# OpenBook_Schematic.net
KiCad netlist of a schematic drawn in EAGLE
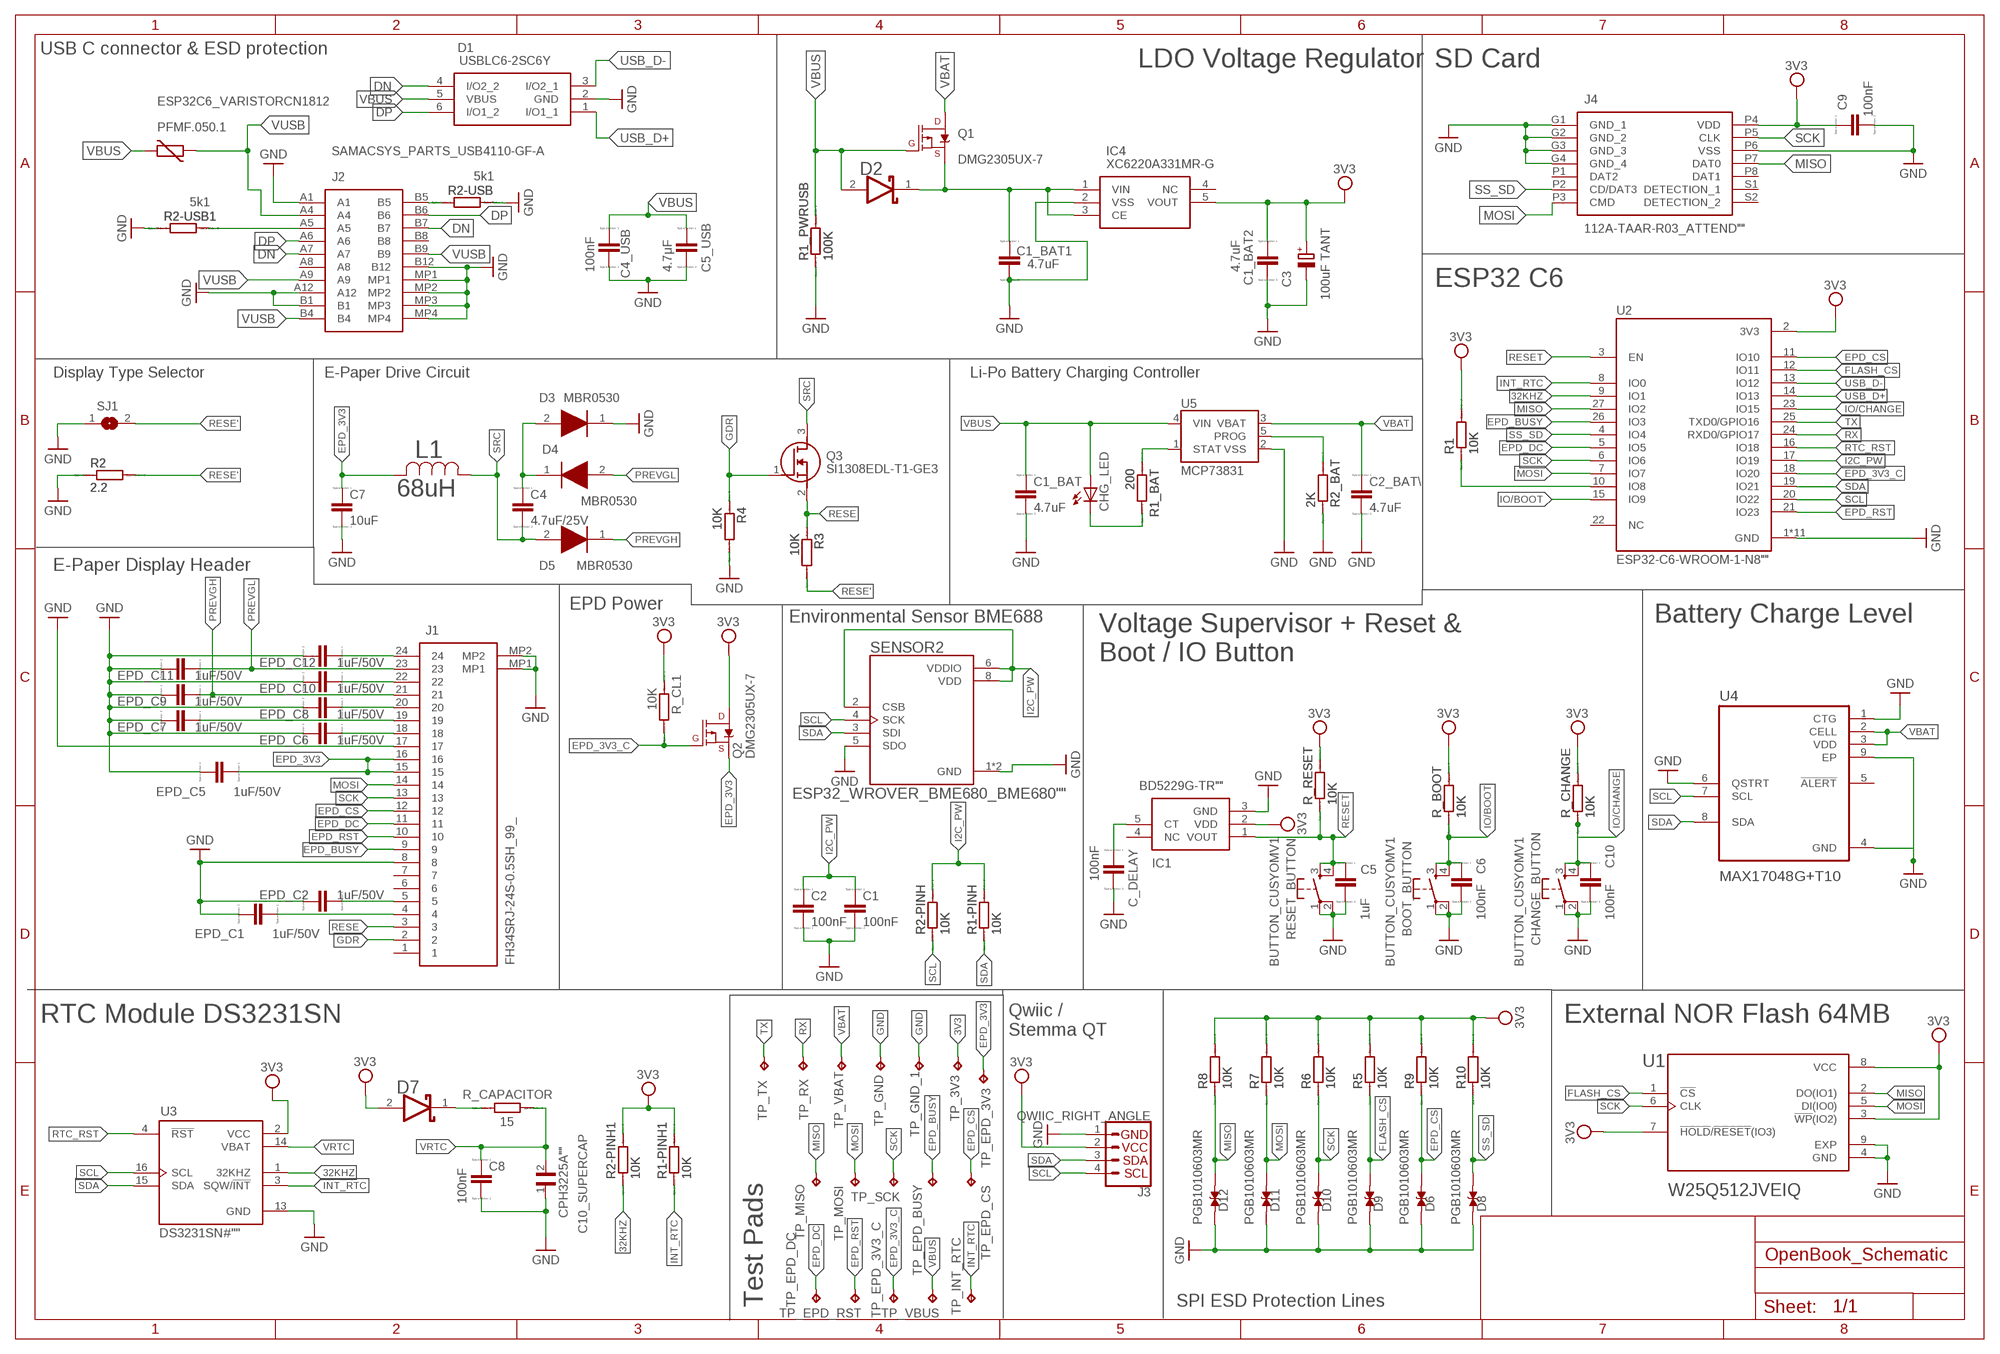
[diagram p0: schematic, sheet 1]

(export (version "E")
  (design (tool "Eeschema 10.0.6"))
  (components
    (comp (ref "BOOT_BUTTON")
      (value "BUTTON_CUSYOMV1")
      (footprint "eagle-import:MYBUTTON")
      (libsource (lib "eagle-import") (part "BUTTON_CUSYOMV1"))
    )
    (comp (ref "C1")
      (value "100nF")
      (footprint "eagle-import:ESP32_WROVER_EAGLE-LTSPICE_C0402")
      (libsource (lib "eagle-import") (part "ESP32_WROVER_EAGLE-LTSPICE_CC0402"))
    )
    (comp (ref "C1_BAT")
      (value "4.7uF")
      (footprint "eagle-import:ESP32_WROVER_EAGLE-LTSPICE_C0402")
      (libsource (lib "eagle-import") (part "ESP32_WROVER_EAGLE-LTSPICE_CC0402"))
    )
    (comp (ref "C1_BAT1")
      (value "4.7uF")
      (footprint "eagle-import:ESP32_WROVER_EAGLE-LTSPICE_C0402")
      (libsource (lib "eagle-import") (part "ESP32_WROVER_EAGLE-LTSPICE_CC0402"))
    )
    (comp (ref "C1_BAT2")
      (value "4.7uF")
      (footprint "eagle-import:ESP32_WROVER_EAGLE-LTSPICE_C0402")
      (libsource (lib "eagle-import") (part "ESP32_WROVER_EAGLE-LTSPICE_CC0402"))
    )
    (comp (ref "C2")
      (value "100nF")
      (footprint "eagle-import:ESP32_WROVER_EAGLE-LTSPICE_C0402")
      (libsource (lib "eagle-import") (part "ESP32_WROVER_EAGLE-LTSPICE_CC0402"))
    )
    (comp (ref "C2_BAT\\")
      (value "4.7uF")
      (footprint "eagle-import:ESP32_WROVER_EAGLE-LTSPICE_C0402")
      (libsource (lib "eagle-import") (part "ESP32_WROVER_EAGLE-LTSPICE_CC0402"))
    )
    (comp (ref "C3")
      (value "100uF TANT")
      (footprint "eagle-import:RCL_CT3528")
      (libsource (lib "eagle-import") (part "RCL_CPOL-EUCT3528"))
    )
    (comp (ref "C4")
      (value "4.7uF/25V")
      (footprint "eagle-import:ESP32_WROVER_EAGLE-LTSPICE_C0402")
      (libsource (lib "eagle-import") (part "ESP32_WROVER_EAGLE-LTSPICE_CC0402"))
    )
    (comp (ref "C4_USB")
      (value "100nF")
      (footprint "eagle-import:ESP32_WROVER_EAGLE-LTSPICE_C0402")
      (libsource (lib "eagle-import") (part "ESP32_WROVER_EAGLE-LTSPICE_CC0402"))
    )
    (comp (ref "C5")
      (value "1uF")
      (footprint "eagle-import:ESP32_WROVER_EAGLE-LTSPICE_C0402")
      (libsource (lib "eagle-import") (part "ESP32_WROVER_EAGLE-LTSPICE_CC0402"))
    )
    (comp (ref "C5_USB")
      (value "4.7μF")
      (footprint "eagle-import:ESP32_WROVER_EAGLE-LTSPICE_C0402")
      (libsource (lib "eagle-import") (part "ESP32_WROVER_EAGLE-LTSPICE_CC0402"))
    )
    (comp (ref "C6")
      (value "100nF")
      (footprint "eagle-import:ESP32_WROVER_EAGLE-LTSPICE_C0402")
      (libsource (lib "eagle-import") (part "ESP32_WROVER_EAGLE-LTSPICE_CC0402"))
    )
    (comp (ref "C7")
      (value "10uF")
      (footprint "eagle-import:ESP32_WROVER_EAGLE-LTSPICE_C0402")
      (libsource (lib "eagle-import") (part "ESP32_WROVER_EAGLE-LTSPICE_CC0402"))
    )
    (comp (ref "C8")
      (value "100nF")
      (footprint "eagle-import:ESP32_WROVER_EAGLE-LTSPICE_C0402")
      (libsource (lib "eagle-import") (part "ESP32_WROVER_EAGLE-LTSPICE_CC0402"))
    )
    (comp (ref "C9")
      (value "100nF")
      (footprint "eagle-import:ESP32_WROVER_EAGLE-LTSPICE_C0402")
      (libsource (lib "eagle-import") (part "EAGLE-LTSPICE_CC0402"))
    )
    (comp (ref "C10")
      (value "100nF")
      (footprint "eagle-import:ESP32_WROVER_EAGLE-LTSPICE_C0402")
      (libsource (lib "eagle-import") (part "ESP32_WROVER_EAGLE-LTSPICE_CC0402"))
    )
    (comp (ref "C10_SUPERCAP")
      (value "CPH3225A\"\"")
      (footprint "eagle-import:CAPCP3225X100N")
      (libsource (lib "eagle-import") (part "CPH3225A{dblquote}{dblquote}"))
    )
    (comp (ref "CHANGE_BUTTON")
      (value "BUTTON_CUSYOMV1")
      (footprint "eagle-import:MYBUTTON")
      (libsource (lib "eagle-import") (part "BUTTON_CUSYOMV1"))
    )
    (comp (ref "CHG_LED")
      (value "ADAFRUIT_LEDCHIP-LED0603")
      (footprint "eagle-import:ADAFRUIT_CHIP-LED0603")
      (libsource (lib "eagle-import") (part "ADAFRUIT_LEDCHIP-LED0603"))
    )
    (comp (ref "C_DELAY")
      (value "100nF")
      (footprint "eagle-import:ESP32_WROVER_EAGLE-LTSPICE_C0402")
      (libsource (lib "eagle-import") (part "ESP32_WROVER_EAGLE-LTSPICE_CC0402"))
    )
    (comp (ref "D1")
      (value "USBLC6-2SC6Y")
      (footprint "eagle-import:SOT95P280X145-6N")
      (libsource (lib "eagle-import") (part "USBLC6-2SC6Y"))
    )
    (comp (ref "D2")
      (value "ESP32_WROVER_AVX---SD0805S020S1R0_AVX_SD0805S020S1R0_0_0AVX_SD0805S020S1R0_0_0")
      (footprint "eagle-import:ESP32_WROVER_AVX---SD0805S020S1R0_AVX_SD0805S020S1R0_0")
      (libsource (lib "eagle-import") (part "ESP32_WROVER_AVX---SD0805S020S1R0_AVX_SD0805S020S1R0_0_0AVX_SD0805S020S1R0_0_0"))
    )
    (comp (ref "D3")
      (value "MBR0530")
      (footprint "eagle-import:SOD3716X135N")
      (libsource (lib "eagle-import") (part "MBR0530"))
    )
    (comp (ref "D4")
      (value "MBR0530")
      (footprint "eagle-import:SOD3716X135N")
      (libsource (lib "eagle-import") (part "MBR0530"))
    )
    (comp (ref "D5")
      (value "MBR0530")
      (footprint "eagle-import:SOD3716X135N")
      (libsource (lib "eagle-import") (part "MBR0530"))
    )
    (comp (ref "D6")
      (value "PGB1010603MR")
      (footprint "eagle-import:DIOC1608X36N")
      (libsource (lib "eagle-import") (part "PGB1010603MR"))
    )
    (comp (ref "D7")
      (value "ESP32_WROVER_AVX---SD0805S020S1R0_AVX_SD0805S020S1R0_0_0AVX_SD0805S020S1R0_0_0")
      (footprint "eagle-import:ESP32_WROVER_AVX---SD0805S020S1R0_AVX_SD0805S020S1R0_0")
      (libsource (lib "eagle-import") (part "ESP32_WROVER_AVX---SD0805S020S1R0_AVX_SD0805S020S1R0_0_0AVX_SD0805S020S1R0_0_0"))
    )
    (comp (ref "D8")
      (value "PGB1010603MR")
      (footprint "eagle-import:DIOC1608X36N")
      (libsource (lib "eagle-import") (part "PGB1010603MR"))
    )
    (comp (ref "D9")
      (value "PGB1010603MR")
      (footprint "eagle-import:DIOC1608X36N")
      (libsource (lib "eagle-import") (part "PGB1010603MR"))
    )
    (comp (ref "D10")
      (value "PGB1010603MR")
      (footprint "eagle-import:DIOC1608X36N")
      (libsource (lib "eagle-import") (part "PGB1010603MR"))
    )
    (comp (ref "D11")
      (value "PGB1010603MR")
      (footprint "eagle-import:DIOC1608X36N")
      (libsource (lib "eagle-import") (part "PGB1010603MR"))
    )
    (comp (ref "D12")
      (value "PGB1010603MR")
      (footprint "eagle-import:DIOC1608X36N")
      (libsource (lib "eagle-import") (part "PGB1010603MR"))
    )
    (comp (ref "EPD_C1")
      (value "1uF/50V")
      (footprint "eagle-import:ESP32_WROVER_EAGLE-LTSPICE_C0402")
      (libsource (lib "eagle-import") (part "ESP32_WROVER_EAGLE-LTSPICE_CC0402"))
    )
    (comp (ref "EPD_C2")
      (value "1uF/50V")
      (footprint "eagle-import:ESP32_WROVER_EAGLE-LTSPICE_C0402")
      (libsource (lib "eagle-import") (part "ESP32_WROVER_EAGLE-LTSPICE_CC0402"))
    )
    (comp (ref "EPD_C5")
      (value "1uF/50V")
      (footprint "eagle-import:ESP32_WROVER_EAGLE-LTSPICE_C0402")
      (libsource (lib "eagle-import") (part "ESP32_WROVER_EAGLE-LTSPICE_CC0402"))
    )
    (comp (ref "EPD_C6")
      (value "1uF/50V")
      (footprint "eagle-import:ESP32_WROVER_EAGLE-LTSPICE_C0402")
      (libsource (lib "eagle-import") (part "ESP32_WROVER_EAGLE-LTSPICE_CC0402"))
    )
    (comp (ref "EPD_C7")
      (value "1uF/50V")
      (footprint "eagle-import:ESP32_WROVER_EAGLE-LTSPICE_C0402")
      (libsource (lib "eagle-import") (part "ESP32_WROVER_EAGLE-LTSPICE_CC0402"))
    )
    (comp (ref "EPD_C8")
      (value "1uF/50V")
      (footprint "eagle-import:ESP32_WROVER_EAGLE-LTSPICE_C0402")
      (libsource (lib "eagle-import") (part "ESP32_WROVER_EAGLE-LTSPICE_CC0402"))
    )
    (comp (ref "EPD_C9")
      (value "1uF/50V")
      (footprint "eagle-import:ESP32_WROVER_EAGLE-LTSPICE_C0402")
      (libsource (lib "eagle-import") (part "ESP32_WROVER_EAGLE-LTSPICE_CC0402"))
    )
    (comp (ref "EPD_C10")
      (value "1uF/50V")
      (footprint "eagle-import:ESP32_WROVER_EAGLE-LTSPICE_C0402")
      (libsource (lib "eagle-import") (part "ESP32_WROVER_EAGLE-LTSPICE_CC0402"))
    )
    (comp (ref "EPD_C11")
      (value "1uF/50V")
      (footprint "eagle-import:ESP32_WROVER_EAGLE-LTSPICE_C0402")
      (libsource (lib "eagle-import") (part "ESP32_WROVER_EAGLE-LTSPICE_CC0402"))
    )
    (comp (ref "EPD_C12")
      (value "1uF/50V")
      (footprint "eagle-import:ESP32_WROVER_EAGLE-LTSPICE_C0402")
      (libsource (lib "eagle-import") (part "ESP32_WROVER_EAGLE-LTSPICE_CC0402"))
    )
    (comp (ref "IC1")
      (value "BD5229G-TR\"\"")
      (footprint "eagle-import:SOT95P280X125-5N")
      (libsource (lib "eagle-import") (part "BD5229G-TR{dblquote}{dblquote}"))
    )
    (comp (ref "IC4")
      (value "XC6220A331MR-G")
      (footprint "eagle-import:SOT95P280X120-5N")
      (libsource (lib "eagle-import") (part "XC6220A331MR-G"))
    )
    (comp (ref "J1")
      (value "FH34SRJ-24S-0.5SH_99_")
      (footprint "eagle-import:FH34SRJ24S05SH99")
      (libsource (lib "eagle-import") (part "FH34SRJ-24S-0.5SH_99_"))
    )
    (comp (ref "J2")
      (value "SAMACSYS_PARTS_USB4110-GF-A")
      (footprint "eagle-import:SAMACSYS_PARTS_USB4110GFA")
      (libsource (lib "eagle-import") (part "SAMACSYS_PARTS_USB4110-GF-A"))
    )
    (comp (ref "J3")
      (value "QWIIC_RIGHT_ANGLE")
      (footprint "eagle-import:JST04_1MM_RA")
      (libsource (lib "eagle-import") (part "QWIIC_CONNECTORJS-1MM"))
    )
    (comp (ref "J4")
      (value "112A-TAAR-R03_ATTEND\"\"")
      (footprint "eagle-import:112ATAARR03ATTEND")
      (libsource (lib "eagle-import") (part "112A-TAAR-R03_ATTEND{dblquote}{dblquote}"))
    )
    (comp (ref "L1")
      (value "68uH")
      (footprint "eagle-import:IND_4828-WE-TPC_WRE")
      (libsource (lib "eagle-import") (part "744043680IND_4828-WE-TPC_WRE"))
    )
    (comp (ref "PFMF.050.1")
      (value "ESP32C6_VARISTORCN1812")
      (footprint "eagle-import:ESP32C6_VARISTOR_CT_CN1812")
      (libsource (lib "eagle-import") (part "ESP32C6_VARISTORCN1812"))
    )
    (comp (ref "Q1")
      (value "20V/4.2A/52mΩ/1.4W")
      (footprint "eagle-import:ESP32_WROVER_SPARKFUN-DISCRETESEMI_SOT23-3")
      (fields (field (name "PARTNAME") "DMG2305UX-7"))
      (libsource (lib "eagle-import") (part "ESP32_WROVER_SPARKFUN-DISCRETESEMI_MOSFET_PCH-DMG2305UX-7"))
    )
    (comp (ref "Q2")
      (value "20V/4.2A/52mΩ/1.4W")
      (footprint "eagle-import:ESP32_WROVER_SPARKFUN-DISCRETESEMI_SOT23-3")
      (fields (field (name "PARTNAME") "DMG2305UX-7"))
      (libsource (lib "eagle-import") (part "ESP32_WROVER_SPARKFUN-DISCRETESEMI_MOSFET_PCH-DMG2305UX-7"))
    )
    (comp (ref "Q3")
      (value "SI1308EDL-T1-GE3")
      (footprint "eagle-import:SOT65P210X110-3N")
      (libsource (lib "eagle-import") (part "SI1308EDL-T1-GE3"))
    )
    (comp (ref "R1")
      (value "10K")
      (footprint "eagle-import:ESP32_WROVER_EAGLE-LTSPICE_R0402")
      (libsource (lib "eagle-import") (part "ESP32_WROVER_EAGLE-LTSPICE_RR0402"))
    )
    (comp (ref "R1-PINH")
      (value "10K")
      (footprint "eagle-import:ESP32_WROVER_EAGLE-LTSPICE_R0402")
      (libsource (lib "eagle-import") (part "ESP32_WROVER_EAGLE-LTSPICE_RR0402"))
    )
    (comp (ref "R1-PINH1")
      (value "10K")
      (footprint "eagle-import:ESP32_WROVER_EAGLE-LTSPICE_R0402")
      (libsource (lib "eagle-import") (part "ESP32_WROVER_EAGLE-LTSPICE_RR0402"))
    )
    (comp (ref "R1_BAT")
      (value "200")
      (footprint "eagle-import:ESP32_WROVER_EAGLE-LTSPICE_R0402")
      (libsource (lib "eagle-import") (part "ESP32_WROVER_EAGLE-LTSPICE_RR0402"))
    )
    (comp (ref "R1_PWRUSB")
      (value "100K")
      (footprint "eagle-import:ESP32_WROVER_EAGLE-LTSPICE_R0402")
      (libsource (lib "eagle-import") (part "ESP32_WROVER_EAGLE-LTSPICE_RR0402"))
    )
    (comp (ref "R2")
      (value "2.2")
      (footprint "eagle-import:ESP32_WROVER_EAGLE-LTSPICE_R0402")
      (libsource (lib "eagle-import") (part "ESP32_WROVER_EAGLE-LTSPICE_RR0402"))
    )
    (comp (ref "R2-PINH")
      (value "10K")
      (footprint "eagle-import:ESP32_WROVER_EAGLE-LTSPICE_R0402")
      (libsource (lib "eagle-import") (part "ESP32_WROVER_EAGLE-LTSPICE_RR0402"))
    )
    (comp (ref "R2-PINH1")
      (value "10K")
      (footprint "eagle-import:ESP32_WROVER_EAGLE-LTSPICE_R0402")
      (libsource (lib "eagle-import") (part "ESP32_WROVER_EAGLE-LTSPICE_RR0402"))
    )
    (comp (ref "R2-USB")
      (value "5k1")
      (footprint "eagle-import:ESP32_WROVER_EAGLE-LTSPICE_R0402")
      (libsource (lib "eagle-import") (part "ESP32_WROVER_EAGLE-LTSPICE_RR0402"))
    )
    (comp (ref "R2-USB1")
      (value "5k1")
      (footprint "eagle-import:ESP32_WROVER_EAGLE-LTSPICE_R0402")
      (libsource (lib "eagle-import") (part "ESP32_WROVER_EAGLE-LTSPICE_RR0402"))
    )
    (comp (ref "R2_BAT")
      (value "2K")
      (footprint "eagle-import:ESP32_WROVER_EAGLE-LTSPICE_R0402")
      (libsource (lib "eagle-import") (part "ESP32_WROVER_EAGLE-LTSPICE_RR0402"))
    )
    (comp (ref "R3")
      (value "10K")
      (footprint "eagle-import:ESP32_WROVER_EAGLE-LTSPICE_R0402")
      (libsource (lib "eagle-import") (part "ESP32_WROVER_EAGLE-LTSPICE_RR0402"))
    )
    (comp (ref "R4")
      (value "10K")
      (footprint "eagle-import:ESP32_WROVER_EAGLE-LTSPICE_R0402")
      (libsource (lib "eagle-import") (part "ESP32_WROVER_EAGLE-LTSPICE_RR0402"))
    )
    (comp (ref "R5")
      (value "10K")
      (footprint "eagle-import:ESP32_WROVER_EAGLE-LTSPICE_R0402")
      (libsource (lib "eagle-import") (part "ESP32_WROVER_EAGLE-LTSPICE_RR0402"))
    )
    (comp (ref "R6")
      (value "10K")
      (footprint "eagle-import:ESP32_WROVER_EAGLE-LTSPICE_R0402")
      (libsource (lib "eagle-import") (part "ESP32_WROVER_EAGLE-LTSPICE_RR0402"))
    )
    (comp (ref "R7")
      (value "10K")
      (footprint "eagle-import:ESP32_WROVER_EAGLE-LTSPICE_R0402")
      (libsource (lib "eagle-import") (part "ESP32_WROVER_EAGLE-LTSPICE_RR0402"))
    )
    (comp (ref "R8")
      (value "10K")
      (footprint "eagle-import:ESP32_WROVER_EAGLE-LTSPICE_R0402")
      (libsource (lib "eagle-import") (part "ESP32_WROVER_EAGLE-LTSPICE_RR0402"))
    )
    (comp (ref "R9")
      (value "10K")
      (footprint "eagle-import:ESP32_WROVER_EAGLE-LTSPICE_R0402")
      (libsource (lib "eagle-import") (part "ESP32_WROVER_EAGLE-LTSPICE_RR0402"))
    )
    (comp (ref "R10")
      (value "10K")
      (footprint "eagle-import:ESP32_WROVER_EAGLE-LTSPICE_R0402")
      (libsource (lib "eagle-import") (part "ESP32_WROVER_EAGLE-LTSPICE_RR0402"))
    )
    (comp (ref "RESET_BUTTON")
      (value "BUTTON_CUSYOMV1")
      (footprint "eagle-import:MYBUTTON")
      (libsource (lib "eagle-import") (part "BUTTON_CUSYOMV1"))
    )
    (comp (ref "R_BOOT")
      (value "10K")
      (footprint "eagle-import:ESP32_WROVER_EAGLE-LTSPICE_R0402")
      (libsource (lib "eagle-import") (part "ESP32_WROVER_EAGLE-LTSPICE_RR0402"))
    )
    (comp (ref "R_CAPACITOR")
      (value "15")
      (footprint "eagle-import:ESP32_WROVER_EAGLE-LTSPICE_R0402")
      (libsource (lib "eagle-import") (part "ESP32_WROVER_EAGLE-LTSPICE_RR0402"))
    )
    (comp (ref "R_CHANGE")
      (value "10K")
      (footprint "eagle-import:ESP32_WROVER_EAGLE-LTSPICE_R0402")
      (libsource (lib "eagle-import") (part "ESP32_WROVER_EAGLE-LTSPICE_RR0402"))
    )
    (comp (ref "R_CL1")
      (value "10K")
      (footprint "eagle-import:ESP32_WROVER_EAGLE-LTSPICE_R0402")
      (libsource (lib "eagle-import") (part "ESP32_WROVER_EAGLE-LTSPICE_RR0402"))
    )
    (comp (ref "R_RESET")
      (value "10K")
      (footprint "eagle-import:ESP32_WROVER_EAGLE-LTSPICE_R0402")
      (libsource (lib "eagle-import") (part "ESP32_WROVER_EAGLE-LTSPICE_RR0402"))
    )
    (comp (ref "SENSOR2")
      (value "ESP32_WROVER_BME680_BME680\"\"")
      (footprint "eagle-import:ESP32_WROVER_BME680_PSON80P300X300X100-8N")
      (libsource (lib "eagle-import") (part "ESP32_WROVER_BME680_BME680{dblquote}{dblquote}"))
    )
    (comp (ref "SJ1") (value "SJ") (footprint "eagle-import:SJ") (libsource (lib "eagle-import") (part "SJ")))
    (comp (ref "TP_3V3")
      (value "TPTP20R")
      (footprint "eagle-import:TP20R")
      (libsource (lib "eagle-import") (part "TPTP20R"))
    )
    (comp (ref "TP_EPD_3V3")
      (value "TPTP20R")
      (footprint "eagle-import:TP20R")
      (libsource (lib "eagle-import") (part "TPTP20R"))
    )
    (comp (ref "TP_EPD_3V3_C")
      (value "TPTP20R")
      (footprint "eagle-import:TP20R")
      (libsource (lib "eagle-import") (part "TPTP20R"))
    )
    (comp (ref "TP_EPD_BUSY")
      (value "TPTP20R")
      (footprint "eagle-import:TP20R")
      (libsource (lib "eagle-import") (part "TPTP20R"))
    )
    (comp (ref "TP_EPD_CS")
      (value "TPTP20R")
      (footprint "eagle-import:TP20R")
      (libsource (lib "eagle-import") (part "TPTP20R"))
    )
    (comp (ref "TP_EPD_DC")
      (value "TPTP20R")
      (footprint "eagle-import:TP20R")
      (libsource (lib "eagle-import") (part "TPTP20R"))
    )
    (comp (ref "TP_EPD_RST")
      (value "TPTP20R")
      (footprint "eagle-import:TP20R")
      (libsource (lib "eagle-import") (part "TPTP20R"))
    )
    (comp (ref "TP_GND")
      (value "TPTP20R")
      (footprint "eagle-import:TP20R")
      (libsource (lib "eagle-import") (part "TPTP20R"))
    )
    (comp (ref "TP_GND_1")
      (value "TPTP20R")
      (footprint "eagle-import:TP20R")
      (libsource (lib "eagle-import") (part "TPTP20R"))
    )
    (comp (ref "TP_INT_RTC")
      (value "TPTP20R")
      (footprint "eagle-import:TP20R")
      (libsource (lib "eagle-import") (part "TPTP20R"))
    )
    (comp (ref "TP_MISO")
      (value "TPTP20R")
      (footprint "eagle-import:TP20R")
      (libsource (lib "eagle-import") (part "TPTP20R"))
    )
    (comp (ref "TP_MOSI")
      (value "TPTP20R")
      (footprint "eagle-import:TP20R")
      (libsource (lib "eagle-import") (part "TPTP20R"))
    )
    (comp (ref "TP_RX")
      (value "TPTP20R")
      (footprint "eagle-import:TP20R")
      (libsource (lib "eagle-import") (part "TPTP20R"))
    )
    (comp (ref "TP_SCK")
      (value "TPTP20R")
      (footprint "eagle-import:TP20R")
      (libsource (lib "eagle-import") (part "TPTP20R"))
    )
    (comp (ref "TP_TX")
      (value "TPTP20R")
      (footprint "eagle-import:TP20R")
      (libsource (lib "eagle-import") (part "TPTP20R"))
    )
    (comp (ref "TP_VBAT")
      (value "TPTP20R")
      (footprint "eagle-import:TP20R")
      (libsource (lib "eagle-import") (part "TPTP20R"))
    )
    (comp (ref "TP_VBUS")
      (value "TPTP20R")
      (footprint "eagle-import:TP20R")
      (libsource (lib "eagle-import") (part "TPTP20R"))
    )
    (comp (ref "U1")
      (value "W25Q512JVEIQ")
      (footprint "eagle-import:SON127P600X800X80-9N")
      (libsource (lib "eagle-import") (part "W25Q512JVEIQ"))
    )
    (comp (ref "U2")
      (value "ESP32-C6-WROOM-1-N8\"\"")
      (footprint "eagle-import:XCVR_ESP32-C6-WROOM-1-N8")
      (libsource (lib "eagle-import") (part "ESP32-C6-WROOM-1-N8{dblquote}{dblquote}"))
    )
    (comp (ref "U3")
      (value "DS3231SN#\"\"")
      (footprint "eagle-import:SOIC127P1032X265-16N")
      (libsource (lib "eagle-import") (part "DS3231SN#{dblquote}{dblquote}"))
    )
    (comp (ref "U4")
      (value "MAX17048G+T10")
      (footprint "eagle-import:SON50P200X200X80-9N")
      (libsource (lib "eagle-import") (part "MAX17048G+T10"))
    )
    (comp (ref "U5")
      (value "MCP73831")
      (footprint "eagle-import:ESP32_WROVER_SPARKFUN-IC-POWER_SOT23-5")
      (libsource (lib "eagle-import") (part "ESP32_WROVER_SPARKFUN-IC-POWER_MCP73831"))
    )
  )
  (nets
    (net (code "1") (name "3V3") (class "Default")
      (node (ref "C1_BAT2") (pin "1") (pinfunction "1_1") (pintype "passive"))
      (node (ref "C3") (pin "+") (pinfunction "+_+") (pintype "passive"))
      (node (ref "C9") (pin "1") (pinfunction "1_1") (pintype "passive"))
      (node (ref "D7") (pin "2") (pinfunction "ANODE_2") (pintype "bidirectional"))
      (node (ref "IC1") (pin "2") (pinfunction "VDD_2") (pintype "bidirectional"))
      (node (ref "IC4") (pin "5") (pinfunction "VOUT_5") (pintype "bidirectional"))
      (node (ref "J3") (pin "2") (pinfunction "2_2") (pintype "power_in"))
      (node (ref "J4") (pin "P4") (pinfunction "VDD_P4") (pintype "bidirectional"))
      (node (ref "Q2") (pin "3") (pinfunction "D_3") (pintype "bidirectional"))
      (node (ref "R1") (pin "2") (pinfunction "2_2") (pintype "passive"))
      (node (ref "R1-PINH1") (pin "2") (pinfunction "2_2") (pintype "passive"))
      (node (ref "R10") (pin "2") (pinfunction "2_2") (pintype "passive"))
      (node (ref "R2-PINH1") (pin "2") (pinfunction "2_2") (pintype "passive"))
      (node (ref "R5") (pin "2") (pinfunction "2_2") (pintype "passive"))
      (node (ref "R6") (pin "2") (pinfunction "2_2") (pintype "passive"))
      (node (ref "R7") (pin "2") (pinfunction "2_2") (pintype "passive"))
      (node (ref "R8") (pin "2") (pinfunction "2_2") (pintype "passive"))
      (node (ref "R9") (pin "2") (pinfunction "2_2") (pintype "passive"))
      (node (ref "R_BOOT") (pin "2") (pinfunction "2_2") (pintype "passive"))
      (node (ref "R_CHANGE") (pin "2") (pinfunction "2_2") (pintype "passive"))
      (node (ref "R_CL1") (pin "1") (pinfunction "1_1") (pintype "passive"))
      (node (ref "R_RESET") (pin "2") (pinfunction "2_2") (pintype "passive"))
      (node (ref "TP_3V3") (pin "TP") (pinfunction "TP_TP") (pintype "input"))
      (node (ref "U1") (pin "3") (pinfunction "~{WP}(IO2)_3") (pintype "bidirectional"))
      (node (ref "U1") (pin "7") (pinfunction "~{HOLD}/~{RESET}(IO3)_7") (pintype "bidirectional"))
      (node (ref "U1") (pin "8") (pinfunction "VCC_8") (pintype "power_in"))
      (node (ref "U2") (pin "2") (pinfunction "3V3_2") (pintype "power_in"))
      (node (ref "U3") (pin "2") (pinfunction "VCC_2") (pintype "power_in"))
    )
    (net (code "2") (name "32KHZ") (class "Default")
      (node (ref "R2-PINH1") (pin "1") (pinfunction "1_1") (pintype "passive"))
      (node (ref "U2") (pin "9") (pinfunction "IO1_9") (pintype "bidirectional"))
      (node (ref "U3") (pin "1") (pinfunction "32KHZ_1") (pintype "output"))
    )
    (net (code "3") (name "DN") (class "Default")
      (node (ref "D1") (pin "4") (pinfunction "I/O2_2_4") (pintype "bidirectional"))
      (node (ref "J2") (pin "A7") (pinfunction "A7_A7") (pintype "bidirectional"))
      (node (ref "J2") (pin "B7") (pinfunction "B7_B7") (pintype "bidirectional"))
    )
    (net (code "4") (name "DP") (class "Default")
      (node (ref "D1") (pin "6") (pinfunction "I/O1_2_6") (pintype "bidirectional"))
      (node (ref "J2") (pin "A6") (pinfunction "A6_A6") (pintype "bidirectional"))
      (node (ref "J2") (pin "B6") (pinfunction "B6_B6") (pintype "bidirectional"))
    )
    (net (code "5") (name "EPD_3V3") (class "Default")
      (node (ref "C7") (pin "1") (pinfunction "1_1") (pintype "passive"))
      (node (ref "EPD_C5") (pin "1") (pinfunction "1_1") (pintype "passive"))
      (node (ref "J1") (pin "15") (pinfunction "15_15") (pintype "bidirectional"))
      (node (ref "J1") (pin "16") (pinfunction "16_16") (pintype "bidirectional"))
      (node (ref "L1") (pin "2") (pinfunction "2_2") (pintype "passive"))
      (node (ref "Q2") (pin "2") (pinfunction "S_2") (pintype "bidirectional"))
      (node (ref "TP_EPD_3V3") (pin "TP") (pinfunction "TP_TP") (pintype "input"))
    )
    (net (code "6") (name "EPD_3V3_C") (class "Default")
      (node (ref "Q2") (pin "1") (pinfunction "G_1") (pintype "bidirectional"))
      (node (ref "R_CL1") (pin "2") (pinfunction "2_2") (pintype "passive"))
      (node (ref "TP_EPD_3V3_C") (pin "TP") (pinfunction "TP_TP") (pintype "input"))
      (node (ref "U2") (pin "18") (pinfunction "IO20_18") (pintype "bidirectional"))
    )
    (net (code "7") (name "EPD_BUSY") (class "Default")
      (node (ref "J1") (pin "9") (pinfunction "9_9") (pintype "bidirectional"))
      (node (ref "TP_EPD_BUSY") (pin "TP") (pinfunction "TP_TP") (pintype "input"))
      (node (ref "U2") (pin "26") (pinfunction "IO3_26") (pintype "bidirectional"))
    )
    (net (code "8") (name "EPD_CS") (class "Default")
      (node (ref "D6") (pin "2") (pinfunction "2_2") (pintype "passive"))
      (node (ref "J1") (pin "12") (pinfunction "12_12") (pintype "bidirectional"))
      (node (ref "R9") (pin "1") (pinfunction "1_1") (pintype "passive"))
      (node (ref "TP_EPD_CS") (pin "TP") (pinfunction "TP_TP") (pintype "input"))
      (node (ref "U2") (pin "11") (pinfunction "IO10_11") (pintype "bidirectional"))
    )
    (net (code "9") (name "EPD_DC") (class "Default")
      (node (ref "J1") (pin "11") (pinfunction "11_11") (pintype "bidirectional"))
      (node (ref "TP_EPD_DC") (pin "TP") (pinfunction "TP_TP") (pintype "input"))
      (node (ref "U2") (pin "5") (pinfunction "IO5_5") (pintype "bidirectional"))
    )
    (net (code "10") (name "EPD_RST") (class "Default")
      (node (ref "J1") (pin "10") (pinfunction "10_10") (pintype "bidirectional"))
      (node (ref "TP_EPD_RST") (pin "TP") (pinfunction "TP_TP") (pintype "input"))
      (node (ref "U2") (pin "21") (pinfunction "IO23_21") (pintype "bidirectional"))
    )
    (net (code "11") (name "FLASH_CS") (class "Default")
      (node (ref "D9") (pin "2") (pinfunction "2_2") (pintype "passive"))
      (node (ref "R5") (pin "1") (pinfunction "1_1") (pintype "passive"))
      (node (ref "U1") (pin "1") (pinfunction "~{CS}_1") (pintype "input"))
      (node (ref "U2") (pin "12") (pinfunction "IO11_12") (pintype "bidirectional"))
    )
    (net (code "12") (name "GDR") (class "Default")
      (node (ref "J1") (pin "2") (pinfunction "2_2") (pintype "bidirectional"))
      (node (ref "Q3") (pin "1") (pinfunction "G_1") (pintype "bidirectional"))
      (node (ref "R4") (pin "1") (pinfunction "1_1") (pintype "passive"))
    )
    (net (code "13") (name "GND") (class "Default")
      (node (ref "BOOT_BUTTON") (pin "1") (pinfunction "1_1") (pintype "passive"))
      (node (ref "BOOT_BUTTON") (pin "2") (pinfunction "2_2") (pintype "passive"))
      (node (ref "C1") (pin "2") (pinfunction "2_2") (pintype "passive"))
      (node (ref "C10") (pin "2") (pinfunction "2_2") (pintype "passive"))
      (node (ref "C10_SUPERCAP") (pin "1") (pinfunction "1_1") (pintype "passive"))
      (node (ref "C1_BAT") (pin "2") (pinfunction "2_2") (pintype "passive"))
      (node (ref "C1_BAT1") (pin "2") (pinfunction "2_2") (pintype "passive"))
      (node (ref "C1_BAT2") (pin "2") (pinfunction "2_2") (pintype "passive"))
      (node (ref "C2") (pin "2") (pinfunction "2_2") (pintype "passive"))
      (node (ref "C2_BAT\\") (pin "2") (pinfunction "2_2") (pintype "passive"))
      (node (ref "C3") (pin "-") (pinfunction "-_-") (pintype "passive"))
      (node (ref "C4_USB") (pin "2") (pinfunction "2_2") (pintype "passive"))
      (node (ref "C5") (pin "2") (pinfunction "2_2") (pintype "passive"))
      (node (ref "C5_USB") (pin "2") (pinfunction "2_2") (pintype "passive"))
      (node (ref "C6") (pin "2") (pinfunction "2_2") (pintype "passive"))
      (node (ref "C7") (pin "2") (pinfunction "2_2") (pintype "passive"))
      (node (ref "C8") (pin "2") (pinfunction "2_2") (pintype "passive"))
      (node (ref "C9") (pin "2") (pinfunction "2_2") (pintype "passive"))
      (node (ref "CHANGE_BUTTON") (pin "1") (pinfunction "1_1") (pintype "passive"))
      (node (ref "CHANGE_BUTTON") (pin "2") (pinfunction "2_2") (pintype "passive"))
      (node (ref "C_DELAY") (pin "2") (pinfunction "2_2") (pintype "passive"))
      (node (ref "D1") (pin "2") (pinfunction "GND_2") (pintype "bidirectional"))
      (node (ref "D10") (pin "1") (pinfunction "1_1") (pintype "passive"))
      (node (ref "D11") (pin "1") (pinfunction "1_1") (pintype "passive"))
      (node (ref "D12") (pin "1") (pinfunction "1_1") (pintype "passive"))
      (node (ref "D3") (pin "1") (pinfunction "K_1") (pintype "bidirectional"))
      (node (ref "D6") (pin "1") (pinfunction "1_1") (pintype "passive"))
      (node (ref "D8") (pin "1") (pinfunction "1_1") (pintype "passive"))
      (node (ref "D9") (pin "1") (pinfunction "1_1") (pintype "passive"))
      (node (ref "EPD_C1") (pin "2") (pinfunction "2_2") (pintype "passive"))
      (node (ref "EPD_C10") (pin "2") (pinfunction "2_2") (pintype "passive"))
      (node (ref "EPD_C11") (pin "2") (pinfunction "2_2") (pintype "passive"))
      (node (ref "EPD_C12") (pin "2") (pinfunction "2_2") (pintype "passive"))
      (node (ref "EPD_C2") (pin "2") (pinfunction "2_2") (pintype "passive"))
      (node (ref "EPD_C5") (pin "2") (pinfunction "2_2") (pintype "passive"))
      (node (ref "EPD_C6") (pin "2") (pinfunction "2_2") (pintype "passive"))
      (node (ref "EPD_C7") (pin "2") (pinfunction "2_2") (pintype "passive"))
      (node (ref "EPD_C8") (pin "2") (pinfunction "2_2") (pintype "passive"))
      (node (ref "EPD_C9") (pin "2") (pinfunction "2_2") (pintype "passive"))
      (node (ref "IC1") (pin "3") (pinfunction "GND_3") (pintype "bidirectional"))
      (node (ref "IC4") (pin "2") (pinfunction "VSS_2") (pintype "bidirectional"))
      (node (ref "J1") (pin "17") (pinfunction "17_17") (pintype "bidirectional"))
      (node (ref "J1") (pin "8") (pinfunction "8_8") (pintype "bidirectional"))
      (node (ref "J1") (pin "MP1") (pinfunction "MP1_MP1") (pintype "bidirectional"))
      (node (ref "J1") (pin "MP2") (pinfunction "MP2_MP2") (pintype "bidirectional"))
      (node (ref "J2") (pin "A1") (pinfunction "A1_A1") (pintype "bidirectional"))
      (node (ref "J2") (pin "A12") (pinfunction "A12_A12") (pintype "bidirectional"))
      (node (ref "J2") (pin "B1") (pinfunction "B1_B1") (pintype "bidirectional"))
      (node (ref "J2") (pin "B12") (pinfunction "B12_B12") (pintype "bidirectional"))
      (node (ref "J2") (pin "MP1") (pinfunction "MP1_MP1") (pintype "bidirectional"))
      (node (ref "J2") (pin "MP2") (pinfunction "MP2_MP2") (pintype "bidirectional"))
      (node (ref "J2") (pin "MP3") (pinfunction "MP3_MP3") (pintype "bidirectional"))
      (node (ref "J2") (pin "MP4") (pinfunction "MP4_MP4") (pintype "bidirectional"))
      (node (ref "J3") (pin "1") (pinfunction "1_1") (pintype "power_in"))
      (node (ref "J4") (pin "G1") (pinfunction "GND_1_G1") (pintype "bidirectional"))
      (node (ref "J4") (pin "G2") (pinfunction "GND_2_G2") (pintype "bidirectional"))
      (node (ref "J4") (pin "G3") (pinfunction "GND_3_G3") (pintype "bidirectional"))
      (node (ref "J4") (pin "G4") (pinfunction "GND_4_G4") (pintype "bidirectional"))
      (node (ref "J4") (pin "P6") (pinfunction "VSS_P6") (pintype "bidirectional"))
      (node (ref "R1_PWRUSB") (pin "1") (pinfunction "1_1") (pintype "passive"))
      (node (ref "R2") (pin "1") (pinfunction "1_1") (pintype "passive"))
      (node (ref "R2-USB") (pin "2") (pinfunction "2_2") (pintype "passive"))
      (node (ref "R2-USB1") (pin "1") (pinfunction "1_1") (pintype "passive"))
      (node (ref "R2_BAT") (pin "1") (pinfunction "1_1") (pintype "passive"))
      (node (ref "R4") (pin "2") (pinfunction "2_2") (pintype "passive"))
      (node (ref "RESET_BUTTON") (pin "1") (pinfunction "1_1") (pintype "passive"))
      (node (ref "RESET_BUTTON") (pin "2") (pinfunction "2_2") (pintype "passive"))
      (node (ref "SENSOR2") (pin "1") (pinfunction "GND_1") (pintype "power_in"))
      (node (ref "SENSOR2") (pin "5") (pinfunction "SDO_5") (pintype "bidirectional"))
      (node (ref "SENSOR2") (pin "7") (pinfunction "GND_7") (pintype "power_in"))
      (node (ref "SJ1") (pin "1") (pinfunction "1_1") (pintype "passive"))
      (node (ref "TP_GND") (pin "TP") (pinfunction "TP_TP") (pintype "input"))
      (node (ref "TP_GND_1") (pin "TP") (pinfunction "TP_TP") (pintype "input"))
      (node (ref "U1") (pin "4") (pinfunction "GND_4") (pintype "power_in"))
      (node (ref "U1") (pin "9") (pinfunction "EXP_9") (pintype "passive"))
      (node (ref "U2") (pin "1") (pinfunction "GND_1") (pintype "power_in"))
      (node (ref "U2") (pin "28") (pinfunction "GND_28") (pintype "power_in"))
      (node (ref "U2") (pin "29_1") (pinfunction "GND_29_1") (pintype "power_in"))
      (node (ref "U2") (pin "29_2") (pinfunction "GND_29_2") (pintype "power_in"))
      (node (ref "U2") (pin "29_3") (pinfunction "GND_29_3") (pintype "power_in"))
      (node (ref "U2") (pin "29_4") (pinfunction "GND_29_4") (pintype "power_in"))
      (node (ref "U2") (pin "29_5") (pinfunction "GND_29_5") (pintype "power_in"))
      (node (ref "U2") (pin "29_6") (pinfunction "GND_29_6") (pintype "power_in"))
      (node (ref "U2") (pin "29_7") (pinfunction "GND_29_7") (pintype "power_in"))
      (node (ref "U2") (pin "29_8") (pinfunction "GND_29_8") (pintype "power_in"))
      (node (ref "U2") (pin "29_9") (pinfunction "GND_29_9") (pintype "power_in"))
      (node (ref "U3") (pin "13") (pinfunction "GND_13") (pintype "power_in"))
      (node (ref "U4") (pin "1") (pinfunction "CTG_1") (pintype "power_in"))
      (node (ref "U4") (pin "4") (pinfunction "GND_4") (pintype "power_in"))
      (node (ref "U4") (pin "6") (pinfunction "QSTRT_6") (pintype "input"))
      (node (ref "U4") (pin "9") (pinfunction "EP_9") (pintype "power_in"))
      (node (ref "U5") (pin "2") (pinfunction "VSS_2") (pintype "power_in"))
    )
    (net (code "14") (name "I2C_PW") (class "Default")
      (node (ref "C1") (pin "1") (pinfunction "1_1") (pintype "passive"))
      (node (ref "C2") (pin "1") (pinfunction "1_1") (pintype "passive"))
      (node (ref "R1-PINH") (pin "2") (pinfunction "2_2") (pintype "passive"))
      (node (ref "R2-PINH") (pin "2") (pinfunction "2_2") (pintype "passive"))
      (node (ref "SENSOR2") (pin "2") (pinfunction "CSB_2") (pintype "input"))
      (node (ref "SENSOR2") (pin "6") (pinfunction "VDDIO_6") (pintype "power_in"))
      (node (ref "SENSOR2") (pin "8") (pinfunction "VDD_8") (pintype "power_in"))
      (node (ref "U2") (pin "17") (pinfunction "IO19_17") (pintype "bidirectional"))
    )
    (net (code "15") (name "INT_RTC") (class "Default")
      (node (ref "R1-PINH1") (pin "1") (pinfunction "1_1") (pintype "passive"))
      (node (ref "TP_INT_RTC") (pin "TP") (pinfunction "TP_TP") (pintype "input"))
      (node (ref "U2") (pin "8") (pinfunction "IO0_8") (pintype "bidirectional"))
      (node (ref "U3") (pin "3") (pinfunction "SQW/~{INT}_3") (pintype "output"))
    )
    (net (code "16") (name "IO{slash}BOOT") (class "Default")
      (node (ref "BOOT_BUTTON") (pin "3") (pinfunction "3_3") (pintype "passive"))
      (node (ref "BOOT_BUTTON") (pin "4") (pinfunction "4_4") (pintype "passive"))
      (node (ref "C6") (pin "1") (pinfunction "1_1") (pintype "passive"))
      (node (ref "R_BOOT") (pin "1") (pinfunction "1_1") (pintype "passive"))
      (node (ref "U2") (pin "15") (pinfunction "IO9_15") (pintype "bidirectional"))
    )
    (net (code "17") (name "IO{slash}CHANGE") (class "Default")
      (node (ref "C10") (pin "1") (pinfunction "1_1") (pintype "passive"))
      (node (ref "CHANGE_BUTTON") (pin "3") (pinfunction "3_3") (pintype "passive"))
      (node (ref "CHANGE_BUTTON") (pin "4") (pinfunction "4_4") (pintype "passive"))
      (node (ref "R_CHANGE") (pin "1") (pinfunction "1_1") (pintype "passive"))
      (node (ref "U2") (pin "23") (pinfunction "IO15_23") (pintype "bidirectional"))
    )
    (net (code "18") (name "MISO") (class "Default")
      (node (ref "D12") (pin "2") (pinfunction "2_2") (pintype "passive"))
      (node (ref "J4") (pin "P7") (pinfunction "DAT0_P7") (pintype "bidirectional"))
      (node (ref "R8") (pin "1") (pinfunction "1_1") (pintype "passive"))
      (node (ref "TP_MISO") (pin "TP") (pinfunction "TP_TP") (pintype "input"))
      (node (ref "U1") (pin "2") (pinfunction "DO(IO1)_2") (pintype "bidirectional"))
      (node (ref "U2") (pin "27") (pinfunction "IO2_27") (pintype "bidirectional"))
    )
    (net (code "19") (name "MOSI") (class "Default")
      (node (ref "D11") (pin "2") (pinfunction "2_2") (pintype "passive"))
      (node (ref "J1") (pin "14") (pinfunction "14_14") (pintype "bidirectional"))
      (node (ref "J4") (pin "P3") (pinfunction "CMD_P3") (pintype "bidirectional"))
      (node (ref "R7") (pin "1") (pinfunction "1_1") (pintype "passive"))
      (node (ref "TP_MOSI") (pin "TP") (pinfunction "TP_TP") (pintype "input"))
      (node (ref "U1") (pin "5") (pinfunction "DI(IO0)_5") (pintype "bidirectional"))
      (node (ref "U2") (pin "7") (pinfunction "IO7_7") (pintype "bidirectional"))
    )
    (net (code "20") (name "Net-(CHG_LED-PadC)") (class "Default")
      (node (ref "CHG_LED") (pin "C") (pinfunction "C_C") (pintype "passive"))
      (node (ref "R1_BAT") (pin "2") (pinfunction "2_2") (pintype "passive"))
    )
    (net (code "21") (name "Net-(D2-CATHODE)") (class "Default")
      (node (ref "C1_BAT1") (pin "1") (pinfunction "1_1") (pintype "passive"))
      (node (ref "D2") (pin "1") (pinfunction "CATHODE_1") (pintype "bidirectional"))
      (node (ref "IC4") (pin "1") (pinfunction "VIN_1") (pintype "bidirectional"))
      (node (ref "IC4") (pin "3") (pinfunction "CE_3") (pintype "bidirectional"))
      (node (ref "Q1") (pin "2") (pinfunction "S_2") (pintype "bidirectional"))
    )
    (net (code "22") (name "Net-(D3-A)") (class "Default")
      (node (ref "C4") (pin "1") (pinfunction "1_1") (pintype "passive"))
      (node (ref "D3") (pin "2") (pinfunction "A_2") (pintype "bidirectional"))
      (node (ref "D4") (pin "1") (pinfunction "K_1") (pintype "bidirectional"))
    )
    (net (code "23") (name "Net-(D7-CATHODE)") (class "Default")
      (node (ref "D7") (pin "1") (pinfunction "CATHODE_1") (pintype "bidirectional"))
      (node (ref "R_CAPACITOR") (pin "2") (pinfunction "2_2") (pintype "passive"))
    )
    (net (code "24") (name "Net-(EPD_C1-Pad1)") (class "Default")
      (node (ref "EPD_C1") (pin "1") (pinfunction "1_1") (pintype "passive"))
      (node (ref "J1") (pin "4") (pinfunction "4_4") (pintype "bidirectional"))
    )
    (net (code "25") (name "Net-(EPD_C2-Pad1)") (class "Default")
      (node (ref "EPD_C2") (pin "1") (pinfunction "1_1") (pintype "passive"))
      (node (ref "J1") (pin "5") (pinfunction "5_5") (pintype "bidirectional"))
    )
    (net (code "26") (name "Net-(EPD_C6-Pad1)") (class "Default")
      (node (ref "EPD_C6") (pin "1") (pinfunction "1_1") (pintype "passive"))
      (node (ref "J1") (pin "18") (pinfunction "18_18") (pintype "bidirectional"))
    )
    (net (code "27") (name "Net-(EPD_C7-Pad1)") (class "Default")
      (node (ref "EPD_C7") (pin "1") (pinfunction "1_1") (pintype "passive"))
      (node (ref "J1") (pin "19") (pinfunction "19_19") (pintype "bidirectional"))
    )
    (net (code "28") (name "Net-(EPD_C8-Pad1)") (class "Default")
      (node (ref "EPD_C8") (pin "1") (pinfunction "1_1") (pintype "passive"))
      (node (ref "J1") (pin "20") (pinfunction "20_20") (pintype "bidirectional"))
    )
    (net (code "29") (name "Net-(EPD_C10-Pad1)") (class "Default")
      (node (ref "EPD_C10") (pin "1") (pinfunction "1_1") (pintype "passive"))
      (node (ref "J1") (pin "22") (pinfunction "22_22") (pintype "bidirectional"))
    )
    (net (code "30") (name "Net-(EPD_C12-Pad1)") (class "Default")
      (node (ref "EPD_C12") (pin "1") (pinfunction "1_1") (pintype "passive"))
      (node (ref "J1") (pin "24") (pinfunction "24_24") (pintype "bidirectional"))
    )
    (net (code "31") (name "Net-(IC1-CT)") (class "Default")
      (node (ref "C_DELAY") (pin "1") (pinfunction "1_1") (pintype "passive"))
      (node (ref "IC1") (pin "5") (pinfunction "CT_5") (pintype "bidirectional"))
    )
    (net (code "32") (name "Net-(J2-PadA5)") (class "Default")
      (node (ref "J2") (pin "A5") (pinfunction "A5_A5") (pintype "bidirectional"))
      (node (ref "R2-USB1") (pin "2") (pinfunction "2_2") (pintype "passive"))
    )
    (net (code "33") (name "Net-(J2-PadB5)") (class "Default")
      (node (ref "J2") (pin "B5") (pinfunction "B5_B5") (pintype "bidirectional"))
      (node (ref "R2-USB") (pin "1") (pinfunction "1_1") (pintype "passive"))
    )
    (net (code "34") (name "Net-(U2-IO8)") (class "Default")
      (node (ref "R1") (pin "1") (pinfunction "1_1") (pintype "passive"))
      (node (ref "U2") (pin "10") (pinfunction "IO8_10") (pintype "bidirectional"))
    )
    (net (code "35") (name "Net-(U5-PROG)") (class "Default")
      (node (ref "R2_BAT") (pin "2") (pinfunction "2_2") (pintype "passive"))
      (node (ref "U5") (pin "5") (pinfunction "PROG_5") (pintype "input"))
    )
    (net (code "36") (name "Net-(U5-STAT)") (class "Default")
      (node (ref "R1_BAT") (pin "1") (pinfunction "1_1") (pintype "passive"))
      (node (ref "U5") (pin "1") (pinfunction "STAT_1") (pintype "output"))
    )
    (net (code "37") (name "PREVGH") (class "Default")
      (node (ref "D5") (pin "1") (pinfunction "K_1") (pintype "bidirectional"))
      (node (ref "EPD_C9") (pin "1") (pinfunction "1_1") (pintype "passive"))
      (node (ref "J1") (pin "21") (pinfunction "21_21") (pintype "bidirectional"))
    )
    (net (code "38") (name "PREVGL") (class "Default")
      (node (ref "D4") (pin "2") (pinfunction "A_2") (pintype "bidirectional"))
      (node (ref "EPD_C11") (pin "1") (pinfunction "1_1") (pintype "passive"))
      (node (ref "J1") (pin "23") (pinfunction "23_23") (pintype "bidirectional"))
    )
    (net (code "39") (name "RESE") (class "Default")
      (node (ref "J1") (pin "3") (pinfunction "3_3") (pintype "bidirectional"))
      (node (ref "Q3") (pin "2") (pinfunction "S_2") (pintype "bidirectional"))
      (node (ref "R3") (pin "1") (pinfunction "1_1") (pintype "passive"))
    )
    (net (code "40") (name "RESE'") (class "Default")
      (node (ref "R2") (pin "2") (pinfunction "2_2") (pintype "passive"))
      (node (ref "R3") (pin "2") (pinfunction "2_2") (pintype "passive"))
      (node (ref "SJ1") (pin "2") (pinfunction "2_2") (pintype "passive"))
    )
    (net (code "41") (name "RESET") (class "Default")
      (node (ref "C5") (pin "1") (pinfunction "1_1") (pintype "passive"))
      (node (ref "IC1") (pin "1") (pinfunction "VOUT_1") (pintype "bidirectional"))
      (node (ref "RESET_BUTTON") (pin "3") (pinfunction "3_3") (pintype "passive"))
      (node (ref "RESET_BUTTON") (pin "4") (pinfunction "4_4") (pintype "passive"))
      (node (ref "R_RESET") (pin "1") (pinfunction "1_1") (pintype "passive"))
      (node (ref "U2") (pin "3") (pinfunction "EN_3") (pintype "input"))
    )
    (net (code "42") (name "RTC_RST") (class "Default")
      (node (ref "U2") (pin "16") (pinfunction "IO18_16") (pintype "bidirectional"))
      (node (ref "U3") (pin "4") (pinfunction "~{RST}_4") (pintype "input"))
    )
    (net (code "43") (name "RX") (class "Default")
      (node (ref "TP_RX") (pin "TP") (pinfunction "TP_TP") (pintype "input"))
      (node (ref "U2") (pin "24") (pinfunction "RXD0/GPIO17_24") (pintype "bidirectional"))
    )
    (net (code "44") (name "SCK") (class "Default")
      (node (ref "D10") (pin "2") (pinfunction "2_2") (pintype "passive"))
      (node (ref "J1") (pin "13") (pinfunction "13_13") (pintype "bidirectional"))
      (node (ref "J4") (pin "P5") (pinfunction "CLK_P5") (pintype "bidirectional"))
      (node (ref "R6") (pin "1") (pinfunction "1_1") (pintype "passive"))
      (node (ref "TP_SCK") (pin "TP") (pinfunction "TP_TP") (pintype "input"))
      (node (ref "U1") (pin "6") (pinfunction "CLK_6") (pintype "input"))
      (node (ref "U2") (pin "6") (pinfunction "IO6_6") (pintype "bidirectional"))
    )
    (net (code "45") (name "SCL") (class "Default")
      (node (ref "J3") (pin "4") (pinfunction "4_4") (pintype "passive"))
      (node (ref "R2-PINH") (pin "1") (pinfunction "1_1") (pintype "passive"))
      (node (ref "SENSOR2") (pin "4") (pinfunction "SCK_4") (pintype "input"))
      (node (ref "U2") (pin "20") (pinfunction "IO22_20") (pintype "bidirectional"))
      (node (ref "U3") (pin "16") (pinfunction "SCL_16") (pintype "input"))
      (node (ref "U4") (pin "7") (pinfunction "SCL_7") (pintype "input"))
    )
    (net (code "46") (name "SDA") (class "Default")
      (node (ref "J3") (pin "3") (pinfunction "3_3") (pintype "passive"))
      (node (ref "R1-PINH") (pin "1") (pinfunction "1_1") (pintype "passive"))
      (node (ref "SENSOR2") (pin "3") (pinfunction "SDI_3") (pintype "bidirectional"))
      (node (ref "U2") (pin "19") (pinfunction "IO21_19") (pintype "bidirectional"))
      (node (ref "U3") (pin "15") (pinfunction "SDA_15") (pintype "bidirectional"))
      (node (ref "U4") (pin "8") (pinfunction "SDA_8") (pintype "bidirectional"))
    )
    (net (code "47") (name "SRC") (class "Default")
      (node (ref "C4") (pin "2") (pinfunction "2_2") (pintype "passive"))
      (node (ref "D5") (pin "2") (pinfunction "A_2") (pintype "bidirectional"))
      (node (ref "L1") (pin "1") (pinfunction "1_1") (pintype "passive"))
      (node (ref "Q3") (pin "3") (pinfunction "D_3") (pintype "bidirectional"))
    )
    (net (code "48") (name "SS_SD") (class "Default")
      (node (ref "D8") (pin "2") (pinfunction "2_2") (pintype "passive"))
      (node (ref "J4") (pin "P2") (pinfunction "CD/DAT3_P2") (pintype "bidirectional"))
      (node (ref "R10") (pin "1") (pinfunction "1_1") (pintype "passive"))
      (node (ref "U2") (pin "4") (pinfunction "IO4_4") (pintype "bidirectional"))
    )
    (net (code "49") (name "TX") (class "Default")
      (node (ref "TP_TX") (pin "TP") (pinfunction "TP_TP") (pintype "input"))
      (node (ref "U2") (pin "25") (pinfunction "TXD0/GPIO16_25") (pintype "bidirectional"))
    )
    (net (code "50") (name "USB_D+") (class "Default")
      (node (ref "D1") (pin "1") (pinfunction "I/O1_1_1") (pintype "bidirectional"))
      (node (ref "U2") (pin "14") (pinfunction "IO13_14") (pintype "bidirectional"))
    )
    (net (code "51") (name "USB_D-") (class "Default")
      (node (ref "D1") (pin "3") (pinfunction "I/O2_1_3") (pintype "bidirectional"))
      (node (ref "U2") (pin "13") (pinfunction "IO12_13") (pintype "bidirectional"))
    )
    (net (code "52") (name "VBAT") (class "Default")
      (node (ref "C2_BAT\\") (pin "1") (pinfunction "1_1") (pintype "passive"))
      (node (ref "Q1") (pin "3") (pinfunction "D_3") (pintype "bidirectional"))
      (node (ref "TP_VBAT") (pin "TP") (pinfunction "TP_TP") (pintype "input"))
      (node (ref "U4") (pin "2") (pinfunction "CELL_2") (pintype "power_in"))
      (node (ref "U4") (pin "3") (pinfunction "VDD_3") (pintype "power_in"))
      (node (ref "U5") (pin "3") (pinfunction "VBAT_3") (pintype "power_in"))
    )
    (net (code "53") (name "VBUS") (class "Default")
      (node (ref "C1_BAT") (pin "1") (pinfunction "1_1") (pintype "passive"))
      (node (ref "C4_USB") (pin "1") (pinfunction "1_1") (pintype "passive"))
      (node (ref "C5_USB") (pin "1") (pinfunction "1_1") (pintype "passive"))
      (node (ref "CHG_LED") (pin "A") (pinfunction "A_A") (pintype "passive"))
      (node (ref "D1") (pin "5") (pinfunction "VBUS_5") (pintype "bidirectional"))
      (node (ref "D2") (pin "2") (pinfunction "ANODE_2") (pintype "bidirectional"))
      (node (ref "PFMF.050.1") (pin "2") (pinfunction "2_2") (pintype "passive"))
      (node (ref "Q1") (pin "1") (pinfunction "G_1") (pintype "bidirectional"))
      (node (ref "R1_PWRUSB") (pin "2") (pinfunction "2_2") (pintype "passive"))
      (node (ref "TP_VBUS") (pin "TP") (pinfunction "TP_TP") (pintype "input"))
      (node (ref "U5") (pin "4") (pinfunction "VIN_4") (pintype "power_in"))
    )
    (net (code "54") (name "VRTC") (class "Default")
      (node (ref "C10_SUPERCAP") (pin "2") (pinfunction "2_2") (pintype "passive"))
      (node (ref "C8") (pin "1") (pinfunction "1_1") (pintype "passive"))
      (node (ref "R_CAPACITOR") (pin "1") (pinfunction "1_1") (pintype "passive"))
      (node (ref "U3") (pin "14") (pinfunction "VBAT_14") (pintype "power_in"))
    )
    (net (code "55") (name "VUSB") (class "Default")
      (node (ref "J2") (pin "A4") (pinfunction "A4_A4") (pintype "bidirectional"))
      (node (ref "J2") (pin "A9") (pinfunction "A9_A9") (pintype "bidirectional"))
      (node (ref "J2") (pin "B4") (pinfunction "B4_B4") (pintype "bidirectional"))
      (node (ref "J2") (pin "B9") (pinfunction "B9_B9") (pintype "bidirectional"))
      (node (ref "PFMF.050.1") (pin "1") (pinfunction "1_1") (pintype "passive"))
    )
    (net (code "56") (name "unconnected-(IC1-NC-Pad4)") (class "Default")
      (node (ref "IC1") (pin "4") (pinfunction "NC_4") (pintype "no_connect"))
    )
    (net (code "57") (name "unconnected-(IC4-NC-Pad4)") (class "Default")
      (node (ref "IC4") (pin "4") (pinfunction "NC_4") (pintype "no_connect"))
    )
    (net (code "58") (name "unconnected-(J1-Pad1)") (class "Default")
      (node (ref "J1") (pin "1") (pinfunction "1_1") (pintype "bidirectional"))
    )
    (net (code "59") (name "unconnected-(J1-Pad6)") (class "Default")
      (node (ref "J1") (pin "6") (pinfunction "6_6") (pintype "bidirectional"))
    )
    (net (code "60") (name "unconnected-(J1-Pad7)") (class "Default")
      (node (ref "J1") (pin "7") (pinfunction "7_7") (pintype "bidirectional"))
    )
    (net (code "61") (name "unconnected-(J2-PadA8)") (class "Default")
      (node (ref "J2") (pin "A8") (pinfunction "A8_A8") (pintype "bidirectional"))
    )
    (net (code "62") (name "unconnected-(J2-PadB8)") (class "Default")
      (node (ref "J2") (pin "B8") (pinfunction "B8_B8") (pintype "bidirectional"))
    )
    (net (code "63") (name "unconnected-(J4-DAT1-PadP8)") (class "Default")
      (node (ref "J4") (pin "P8") (pinfunction "DAT1_P8") (pintype "bidirectional"))
    )
    (net (code "64") (name "unconnected-(J4-DAT2-PadP1)") (class "Default")
      (node (ref "J4") (pin "P1") (pinfunction "DAT2_P1") (pintype "bidirectional"))
    )
    (net (code "65") (name "unconnected-(J4-DETECTION_1-PadS1)") (class "Default")
      (node (ref "J4") (pin "S1") (pinfunction "DETECTION_1_S1") (pintype "bidirectional"))
    )
    (net (code "66") (name "unconnected-(J4-DETECTION_2-PadS2)") (class "Default")
      (node (ref "J4") (pin "S2") (pinfunction "DETECTION_2_S2") (pintype "bidirectional"))
    )
    (net (code "67") (name "unconnected-(U2-NC-Pad22)") (class "Default")
      (node (ref "U2") (pin "22") (pinfunction "NC_22") (pintype "no_connect"))
    )
    (net (code "68") (name "unconnected-(U4-~{ALERT}-Pad5)") (class "Default")
      (node (ref "U4") (pin "5") (pinfunction "~{ALERT}_5") (pintype "output"))
    )
  )
)
